# MCU.net
KiCad netlist of a schematic drawn in Altium Designer
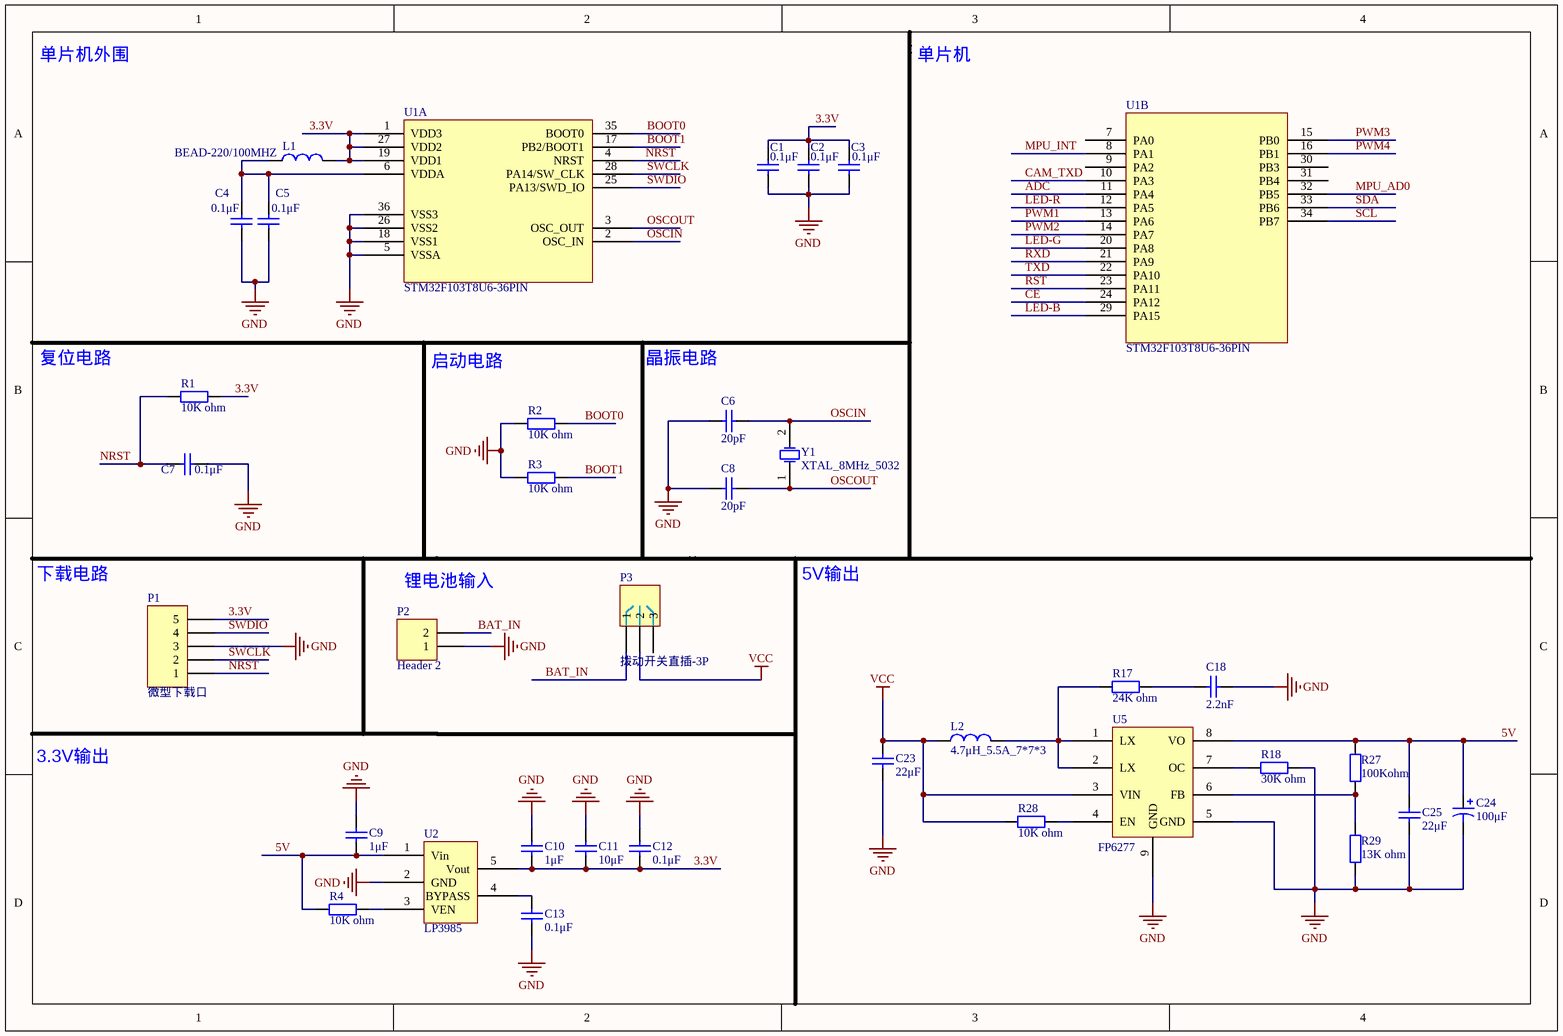
[diagram p0: MCU.SchDoc]

(export (version "E")
  (design (tool "Eeschema 10.0.6"))
  (components
    (comp (ref "C1")
      (value "0.1μF")
      (footprint "0603C")
      (description "0.1μF_50V,X7R,±5%")
      (libsource (lib "Yang_Lib") (part "Cap_0.1μF_50V_0603"))
    )
    (comp (ref "C2")
      (value "0.1μF")
      (footprint "0603C")
      (description "0.1μF_50V,X7R,±5%")
      (libsource (lib "Yang_Lib") (part "Cap_0.1μF_50V_0603"))
    )
    (comp (ref "C3")
      (value "0.1μF")
      (footprint "0603C")
      (description "0.1μF_50V,X7R,±5%")
      (libsource (lib "Yang_Lib") (part "Cap_0.1μF_50V_0603"))
    )
    (comp (ref "C4")
      (value "0.1μF")
      (footprint "0603C")
      (description "0.1μF_50V,X7R,±5%")
      (libsource (lib "Yang_Lib") (part "Cap_0.1μF_50V_0603"))
    )
    (comp (ref "C5")
      (value "0.1μF")
      (footprint "0603C")
      (description "0.1μF_50V,X7R,±5%")
      (libsource (lib "Yang_Lib") (part "Cap_0.1μF_50V_0603"))
    )
    (comp (ref "C6")
      (value "20pF")
      (footprint "0603C")
      (description "20pF_50V,CH,±5%")
      (libsource (lib "Yang_Lib") (part "Cap_20pF_50V_0603"))
    )
    (comp (ref "C7")
      (value "0.1μF")
      (footprint "0603C")
      (description "0.1μF_50V,X7R,±5%")
      (libsource (lib "Yang_Lib") (part "Cap_0.1μF_50V_0603"))
    )
    (comp (ref "C8")
      (value "20pF")
      (footprint "0603C")
      (description "20pF_50V,CH,±5%")
      (libsource (lib "Yang_Lib") (part "Cap_20pF_50V_0603"))
    )
    (comp (ref "C9")
      (value "1μF")
      (footprint "0603C")
      (description "1μF_50V,X5R,±10%")
      (libsource (lib "Yang_Lib") (part "Cap_1μF_50V_0603"))
    )
    (comp (ref "C10")
      (value "1μF")
      (footprint "0603C")
      (description "1μF_50V,X5R,±10%")
      (libsource (lib "Yang_Lib") (part "Cap_1μF_50V_0603"))
    )
    (comp (ref "C11")
      (value "10μF")
      (footprint "0603C")
      (description "10μF_35V,X5R,20%")
      (libsource (lib "Yang_Lib") (part "Cap_10μF_35V_0603"))
    )
    (comp (ref "C12")
      (value "0.1μF")
      (footprint "0603C")
      (description "0.1μF_50V,X7R,±5%")
      (libsource (lib "Yang_Lib") (part "Cap_0.1μF_50V_0603"))
    )
    (comp (ref "C13")
      (value "0.1μF")
      (footprint "0603C")
      (description "0.1μF_50V,X7R,±5%")
      (libsource (lib "Yang_Lib") (part "Cap_0.1μF_50V_0603"))
    )
    (comp (ref "C18")
      (value "2.2nF")
      (footprint "0603C")
      (description "2.2nF_50V,X7R,10%")
      (libsource (lib "Yang_Lib") (part "Cap_2.2nF_50V_0603"))
    )
    (comp (ref "C23")
      (value "22μF")
      (footprint "1206C")
      (description "22μF_35V,20%")
      (libsource (lib "Yang_Lib") (part "Cap_22μF_35V_1206"))
    )
    (comp (ref "C24")
      (value "100μF")
      (footprint "D7343C")
      (description "100μF_16V")
      (libsource (lib "Yang_Lib") (part "Cap_100μF_16V_D7343"))
    )
    (comp (ref "C25")
      (value "22μF")
      (footprint "1206C")
      (description "22μF_35V,20%")
      (libsource (lib "Yang_Lib") (part "Cap_22μF_35V_1206"))
    )
    (comp (ref "L1")
      (value "BEAD-220/100MHZ")
      (footprint "0603R")
      (libsource (lib "Yang_Lib") (part "BEAD-220/100MHZ_0603"))
    )
    (comp (ref "L2")
      (value "4.7μH_5.5A_7*7*3")
      (footprint "7*7*3mm - 06030")
      (description "4.7μH_5.5A_")
      (libsource (lib "Yang_Lib") (part "4.7μH_5.5A_7*7*3"))
    )
    (comp (ref "P1") (value "微型下载口") (footprint "微型下载口") (libsource (lib "Yang_Lib") (part "微型下载口")))
    (comp (ref "P2")
      (value "Header 2")
      (footprint "HDR1X2")
      (description "Header, 2-Pin")
      (fields (field (name "PUBLISHER") "Altium Limited"))
      (libsource (lib "Miscellaneous Connectors") (part "Header 2"))
    )
    (comp (ref "P3")
      (value "拨动开关直插-3P")
      (footprint "拨动开关-3P")
      (libsource (lib "Yang_Lib") (part "拨动开关直插-3P"))
    )
    (comp (ref "R1")
      (value "10K ohm")
      (footprint "0603R")
      (description "10K ohm,1%")
      (libsource (lib "Yang_Lib") (part "Res_10K ohm_0603"))
    )
    (comp (ref "R2")
      (value "10K ohm")
      (footprint "0603R")
      (description "10K ohm,1%")
      (libsource (lib "Yang_Lib") (part "Res_10K ohm_0603"))
    )
    (comp (ref "R3")
      (value "10K ohm")
      (footprint "0603R")
      (description "10K ohm,1%")
      (libsource (lib "Yang_Lib") (part "Res_10K ohm_0603"))
    )
    (comp (ref "R4")
      (value "10K ohm")
      (footprint "0603R")
      (description "10K ohm,1%")
      (libsource (lib "Yang_Lib") (part "Res_10K ohm_0603"))
    )
    (comp (ref "R17")
      (value "24K ohm")
      (footprint "0603R")
      (description "24K ohm,1%")
      (libsource (lib "Yang_Lib") (part "Res_24K ohm_0603"))
    )
    (comp (ref "R18")
      (value "30K ohm")
      (footprint "0603R")
      (description "30K ohm,1%")
      (libsource (lib "Yang_Lib") (part "Res_30K ohm_0603"))
    )
    (comp (ref "R27")
      (value "100Kohm")
      (footprint "0603R")
      (description "100K ohm_5%")
      (libsource (lib "Yang_Lib") (part "Res_100Kohm_0603"))
    )
    (comp (ref "R28")
      (value "10K ohm")
      (footprint "0603R")
      (description "10K ohm,1%")
      (libsource (lib "Yang_Lib") (part "Res_10K ohm_0603"))
    )
    (comp (ref "R29")
      (value "13K ohm")
      (footprint "0603R")
      (description "13K ohm,1%")
      (libsource (lib "Yang_Lib") (part "Res_13K ohm_0603"))
    )
    (comp (ref "U1")
      (value "STM32F103T8U6-36PIN")
      (footprint "QFN-36N")
      (libsource (lib "Yang_Lib") (part "STM32F103T8U6-36PIN"))
    )
    (comp (ref "U2") (value "LP3985") (footprint "SOT-23-5") (libsource (lib "Yang_Lib") (part "LP3985")))
    (comp (ref "U5") (value "FP6277") (footprint "SO8 - FP6277") (libsource (lib "Yang_Lib") (part "FP6277")))
    (comp (ref "Y1")
      (value "XTAL_8MHz_5032")
      (footprint "5032")
      (description "XTAL_8MHz")
      (libsource (lib "Yang_Lib") (part "XTAL_8MHz_5032"))
    )
  )
  (nets
    (net (code "1") (name "/3.3V") (class "Default")
      (node (ref "C1") (pin "2") (pinfunction "2_2") (pintype "passive"))
      (node (ref "C10") (pin "2") (pinfunction "2_2") (pintype "passive"))
      (node (ref "C11") (pin "1") (pinfunction "1_1") (pintype "passive"))
      (node (ref "C12") (pin "1") (pinfunction "1_1") (pintype "passive"))
      (node (ref "C2") (pin "2") (pinfunction "2_2") (pintype "passive"))
      (node (ref "C3") (pin "2") (pinfunction "2_2") (pintype "passive"))
      (node (ref "L1") (pin "2") (pinfunction "2_2") (pintype "passive"))
      (node (ref "P1") (pin "5") (pinfunction "5_5") (pintype "passive"))
      (node (ref "R1") (pin "2") (pinfunction "2_2") (pintype "passive"))
      (node (ref "U1") (pin "1") (pinfunction "VDD3_1") (pintype "passive"))
      (node (ref "U1") (pin "19") (pinfunction "VDD1_19") (pintype "passive"))
      (node (ref "U1") (pin "27") (pinfunction "VDD2_27") (pintype "passive"))
      (node (ref "U2") (pin "5") (pinfunction "Vout_5") (pintype "passive"))
    )
    (net (code "2") (name "/5V") (class "Default")
      (node (ref "C24") (pin "1") (pinfunction "1_1") (pintype "passive"))
      (node (ref "C25") (pin "2") (pinfunction "2_2") (pintype "passive"))
      (node (ref "C9") (pin "2") (pinfunction "2_2") (pintype "passive"))
      (node (ref "R27") (pin "2") (pinfunction "2_2") (pintype "passive"))
      (node (ref "R4") (pin "1") (pinfunction "1_1") (pintype "passive"))
      (node (ref "U2") (pin "1") (pinfunction "Vin_1") (pintype "passive"))
      (node (ref "U5") (pin "8") (pinfunction "VO_8") (pintype "passive"))
    )
    (net (code "3") (name "/ADC") (class "Default")
      (node (ref "U1") (pin "11") (pinfunction "PA4_11") (pintype "passive"))
    )
    (net (code "4") (name "/BAT_IN") (class "Default")
      (node (ref "P2") (pin "2") (pinfunction "2_2") (pintype "passive"))
      (node (ref "P3") (pin "1") (pinfunction "1_1") (pintype "passive"))
    )
    (net (code "5") (name "/BOOT0") (class "Default")
      (node (ref "R2") (pin "2") (pinfunction "2_2") (pintype "passive"))
      (node (ref "U1") (pin "35") (pinfunction "BOOT0_35") (pintype "passive"))
    )
    (net (code "6") (name "/BOOT1") (class "Default")
      (node (ref "R3") (pin "2") (pinfunction "2_2") (pintype "passive"))
      (node (ref "U1") (pin "17") (pinfunction "PB2/BOOT1_17") (pintype "passive"))
    )
    (net (code "7") (name "/CAM_TXD") (class "Default")
      (node (ref "U1") (pin "10") (pinfunction "PA3_10") (pintype "passive"))
    )
    (net (code "8") (name "/CE") (class "Default")
      (node (ref "U1") (pin "24") (pinfunction "PA12_24") (pintype "passive"))
    )
    (net (code "9") (name "/LED-B") (class "Default")
      (node (ref "U1") (pin "29") (pinfunction "PA15_29") (pintype "passive"))
    )
    (net (code "10") (name "/LED-G") (class "Default")
      (node (ref "U1") (pin "20") (pinfunction "PA8_20") (pintype "passive"))
    )
    (net (code "11") (name "/LED-R") (class "Default")
      (node (ref "U1") (pin "12") (pinfunction "PA5_12") (pintype "passive"))
    )
    (net (code "12") (name "/MPU_AD0") (class "Default")
      (node (ref "U1") (pin "32") (pinfunction "PB5_32") (pintype "passive"))
    )
    (net (code "13") (name "/MPU_INT") (class "Default")
      (node (ref "U1") (pin "8") (pinfunction "PA1_8") (pintype "passive"))
    )
    (net (code "14") (name "/NRST") (class "Default")
      (node (ref "C7") (pin "2") (pinfunction "2_2") (pintype "passive"))
      (node (ref "P1") (pin "1") (pinfunction "1_1") (pintype "passive"))
      (node (ref "R1") (pin "1") (pinfunction "1_1") (pintype "passive"))
      (node (ref "U1") (pin "4") (pinfunction "NRST_4") (pintype "passive"))
    )
    (net (code "15") (name "/OSCIN") (class "Default")
      (node (ref "C6") (pin "2") (pinfunction "2_2") (pintype "passive"))
      (node (ref "U1") (pin "2") (pinfunction "OSC_IN_2") (pintype "passive"))
      (node (ref "Y1") (pin "2") (pinfunction "OSC2_2") (pintype "passive"))
    )
    (net (code "16") (name "/OSCOUT") (class "Default")
      (node (ref "C8") (pin "2") (pinfunction "2_2") (pintype "passive"))
      (node (ref "U1") (pin "3") (pinfunction "OSC_OUT_3") (pintype "passive"))
      (node (ref "Y1") (pin "1") (pinfunction "OSC1_1") (pintype "passive"))
    )
    (net (code "17") (name "/PWM1") (class "Default")
      (node (ref "U1") (pin "13") (pinfunction "PA6_13") (pintype "passive"))
    )
    (net (code "18") (name "/PWM2") (class "Default")
      (node (ref "U1") (pin "14") (pinfunction "PA7_14") (pintype "passive"))
    )
    (net (code "19") (name "/PWM3") (class "Default")
      (node (ref "U1") (pin "15") (pinfunction "PB0_15") (pintype "passive"))
    )
    (net (code "20") (name "/PWM4") (class "Default")
      (node (ref "U1") (pin "16") (pinfunction "PB1_16") (pintype "passive"))
    )
    (net (code "21") (name "/RST") (class "Default")
      (node (ref "U1") (pin "23") (pinfunction "PA11_23") (pintype "passive"))
    )
    (net (code "22") (name "/RXD") (class "Default")
      (node (ref "U1") (pin "21") (pinfunction "PA9_21") (pintype "passive"))
    )
    (net (code "23") (name "/SCL") (class "Default")
      (node (ref "U1") (pin "34") (pinfunction "PB7_34") (pintype "passive"))
    )
    (net (code "24") (name "/SDA") (class "Default")
      (node (ref "U1") (pin "33") (pinfunction "PB6_33") (pintype "passive"))
    )
    (net (code "25") (name "/SWCLK") (class "Default")
      (node (ref "P1") (pin "2") (pinfunction "2_2") (pintype "passive"))
      (node (ref "U1") (pin "28") (pinfunction "PA14/SW_CLK_28") (pintype "passive"))
    )
    (net (code "26") (name "/SWDIO") (class "Default")
      (node (ref "P1") (pin "4") (pinfunction "4_4") (pintype "passive"))
      (node (ref "U1") (pin "25") (pinfunction "PA13/SWD_IO_25") (pintype "passive"))
    )
    (net (code "27") (name "/TXD") (class "Default")
      (node (ref "U1") (pin "22") (pinfunction "PA10_22") (pintype "passive"))
    )
    (net (code "28") (name "GND") (class "Default")
      (node (ref "C1") (pin "1") (pinfunction "1_1") (pintype "passive"))
      (node (ref "C10") (pin "1") (pinfunction "1_1") (pintype "passive"))
      (node (ref "C11") (pin "2") (pinfunction "2_2") (pintype "passive"))
      (node (ref "C12") (pin "2") (pinfunction "2_2") (pintype "passive"))
      (node (ref "C13") (pin "1") (pinfunction "1_1") (pintype "passive"))
      (node (ref "C18") (pin "1") (pinfunction "1_1") (pintype "passive"))
      (node (ref "C2") (pin "1") (pinfunction "1_1") (pintype "passive"))
      (node (ref "C23") (pin "1") (pinfunction "1_1") (pintype "passive"))
      (node (ref "C24") (pin "2") (pinfunction "2_2") (pintype "passive"))
      (node (ref "C25") (pin "1") (pinfunction "1_1") (pintype "passive"))
      (node (ref "C3") (pin "1") (pinfunction "1_1") (pintype "passive"))
      (node (ref "C4") (pin "1") (pinfunction "1_1") (pintype "passive"))
      (node (ref "C5") (pin "1") (pinfunction "1_1") (pintype "passive"))
      (node (ref "C6") (pin "1") (pinfunction "1_1") (pintype "passive"))
      (node (ref "C7") (pin "1") (pinfunction "1_1") (pintype "passive"))
      (node (ref "C8") (pin "1") (pinfunction "1_1") (pintype "passive"))
      (node (ref "C9") (pin "1") (pinfunction "1_1") (pintype "passive"))
      (node (ref "P1") (pin "3") (pinfunction "3_3") (pintype "passive"))
      (node (ref "P2") (pin "1") (pinfunction "1_1") (pintype "passive"))
      (node (ref "R18") (pin "2") (pinfunction "2_2") (pintype "passive"))
      (node (ref "R2") (pin "1") (pinfunction "1_1") (pintype "passive"))
      (node (ref "R29") (pin "1") (pinfunction "1_1") (pintype "passive"))
      (node (ref "R3") (pin "1") (pinfunction "1_1") (pintype "passive"))
      (node (ref "U1") (pin "18") (pinfunction "VSS1_18") (pintype "passive"))
      (node (ref "U1") (pin "26") (pinfunction "VSS2_26") (pintype "passive"))
      (node (ref "U1") (pin "36") (pinfunction "VSS3_36") (pintype "passive"))
      (node (ref "U1") (pin "5") (pinfunction "VSSA_5") (pintype "passive"))
      (node (ref "U2") (pin "2") (pinfunction "GND_2") (pintype "passive"))
      (node (ref "U5") (pin "5") (pinfunction "GND_5") (pintype "passive"))
      (node (ref "U5") (pin "9") (pinfunction "GND_9") (pintype "passive"))
    )
    (net (code "29") (name "Net-(C18-Pad2)") (class "Default")
      (node (ref "C18") (pin "2") (pinfunction "2_2") (pintype "passive"))
      (node (ref "R17") (pin "1") (pinfunction "1_1") (pintype "passive"))
    )
    (net (code "30") (name "Net-(L2-Pad2)") (class "Default")
      (node (ref "L2") (pin "2") (pinfunction "2_2") (pintype "passive"))
      (node (ref "R17") (pin "2") (pinfunction "2_2") (pintype "passive"))
      (node (ref "U5") (pin "1") (pinfunction "LX_1") (pintype "passive"))
      (node (ref "U5") (pin "2") (pinfunction "LX_2") (pintype "passive"))
    )
    (net (code "31") (name "Net-(U1A-VDDA)") (class "Default")
      (node (ref "C4") (pin "2") (pinfunction "2_2") (pintype "passive"))
      (node (ref "C5") (pin "2") (pinfunction "2_2") (pintype "passive"))
      (node (ref "L1") (pin "1") (pinfunction "1_1") (pintype "passive"))
      (node (ref "U1") (pin "6") (pinfunction "VDDA_6") (pintype "passive"))
    )
    (net (code "32") (name "Net-(U2-BYPASS)") (class "Default")
      (node (ref "C13") (pin "2") (pinfunction "2_2") (pintype "passive"))
      (node (ref "U2") (pin "4") (pinfunction "BYPASS_4") (pintype "passive"))
    )
    (net (code "33") (name "Net-(U2-VEN)") (class "Default")
      (node (ref "R4") (pin "2") (pinfunction "2_2") (pintype "passive"))
      (node (ref "U2") (pin "3") (pinfunction "VEN_3") (pintype "passive"))
    )
    (net (code "34") (name "Net-(U5-EN)") (class "Default")
      (node (ref "R28") (pin "2") (pinfunction "2_2") (pintype "passive"))
      (node (ref "U5") (pin "4") (pinfunction "EN_4") (pintype "passive"))
    )
    (net (code "35") (name "Net-(U5-FB)") (class "Default")
      (node (ref "R27") (pin "1") (pinfunction "1_1") (pintype "passive"))
      (node (ref "R29") (pin "2") (pinfunction "2_2") (pintype "passive"))
      (node (ref "U5") (pin "6") (pinfunction "FB_6") (pintype "passive"))
    )
    (net (code "36") (name "Net-(U5-OC)") (class "Default")
      (node (ref "R18") (pin "1") (pinfunction "1_1") (pintype "passive"))
      (node (ref "U5") (pin "7") (pinfunction "OC_7") (pintype "passive"))
    )
    (net (code "37") (name "VCC") (class "Default")
      (node (ref "C23") (pin "2") (pinfunction "2_2") (pintype "passive"))
      (node (ref "L2") (pin "1") (pinfunction "1_1") (pintype "passive"))
      (node (ref "P3") (pin "2") (pinfunction "2_2") (pintype "passive"))
      (node (ref "R28") (pin "1") (pinfunction "1_1") (pintype "passive"))
      (node (ref "U5") (pin "3") (pinfunction "VIN_3") (pintype "passive"))
    )
    (net (code "38") (name "unconnected-(P3-Pad3)") (class "Default")
      (node (ref "P3") (pin "3") (pinfunction "3_3") (pintype "passive"))
    )
    (net (code "39") (name "unconnected-(U1B-PA0-Pad7)") (class "Default")
      (node (ref "U1") (pin "7") (pinfunction "PA0_7") (pintype "passive"))
    )
    (net (code "40") (name "unconnected-(U1B-PA2-Pad9)") (class "Default")
      (node (ref "U1") (pin "9") (pinfunction "PA2_9") (pintype "passive"))
    )
    (net (code "41") (name "unconnected-(U1B-PB3-Pad30)") (class "Default")
      (node (ref "U1") (pin "30") (pinfunction "PB3_30") (pintype "passive"))
    )
    (net (code "42") (name "unconnected-(U1B-PB4-Pad31)") (class "Default")
      (node (ref "U1") (pin "31") (pinfunction "PB4_31") (pintype "passive"))
    )
  )
)
